# SMS-3923-081-breakout.net
KiCad netlist of a schematic drawn in EAGLE
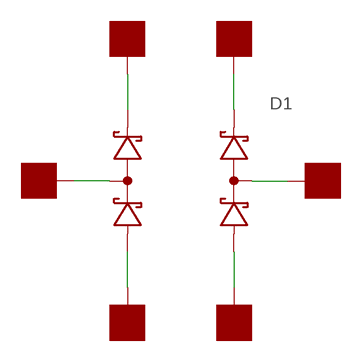
[diagram p0: schematic, sheet 1]

(export (version "E")
  (design (tool "Eeschema 10.0.6"))
  (components
    (comp (ref "D1")
      (value "SMS3923-081")
      (footprint "eagle-import:SC-88")
      (libsource (lib "eagle-import") (part "SMS3923-081"))
    )
    (comp (ref "U$1")
      (value "PAD50MIL")
      (footprint "eagle-import:PAD_50MIL")
      (libsource (lib "eagle-import") (part "PAD50MIL"))
    )
    (comp (ref "U$2")
      (value "PAD50MIL")
      (footprint "eagle-import:PAD_50MIL")
      (libsource (lib "eagle-import") (part "PAD50MIL"))
    )
    (comp (ref "U$3")
      (value "PAD50MIL")
      (footprint "eagle-import:PAD_50MIL")
      (libsource (lib "eagle-import") (part "PAD50MIL"))
    )
    (comp (ref "U$4")
      (value "PAD50MIL")
      (footprint "eagle-import:PAD_50MIL")
      (libsource (lib "eagle-import") (part "PAD50MIL"))
    )
    (comp (ref "U$5")
      (value "PAD50MIL")
      (footprint "eagle-import:PAD_50MIL")
      (libsource (lib "eagle-import") (part "PAD50MIL"))
    )
    (comp (ref "U$6")
      (value "PAD50MIL")
      (footprint "eagle-import:PAD_50MIL")
      (libsource (lib "eagle-import") (part "PAD50MIL"))
    )
  )
  (nets
    (net (code "1") (name "Net-(D1-ANODE0)") (class "Default")
      (node (ref "D1") (pin "1") (pinfunction "ANODE0_1") (pintype "bidirectional"))
      (node (ref "U$4") (pin "P$1") (pinfunction "P$1_P$1") (pintype "bidirectional"))
    )
    (net (code "2") (name "Net-(D1-ANODE1)") (class "Default")
      (node (ref "D1") (pin "6") (pinfunction "ANODE1_6") (pintype "bidirectional"))
      (node (ref "U$3") (pin "P$1") (pinfunction "P$1_P$1") (pintype "bidirectional"))
    )
    (net (code "3") (name "Net-(D1-CATHODE0)") (class "Default")
      (node (ref "D1") (pin "3") (pinfunction "CATHODE0_3") (pintype "bidirectional"))
      (node (ref "U$1") (pin "P$1") (pinfunction "P$1_P$1") (pintype "bidirectional"))
    )
    (net (code "4") (name "Net-(D1-CATHODE1)") (class "Default")
      (node (ref "D1") (pin "4") (pinfunction "CATHODE1_4") (pintype "bidirectional"))
      (node (ref "U$2") (pin "P$1") (pinfunction "P$1_P$1") (pintype "bidirectional"))
    )
    (net (code "5") (name "Net-(D1-COMMON0)") (class "Default")
      (node (ref "D1") (pin "2") (pinfunction "COMMON0_2") (pintype "bidirectional"))
      (node (ref "U$5") (pin "P$1") (pinfunction "P$1_P$1") (pintype "bidirectional"))
    )
    (net (code "6") (name "Net-(D1-COMMON1)") (class "Default")
      (node (ref "D1") (pin "5") (pinfunction "COMMON1_5") (pintype "bidirectional"))
      (node (ref "U$6") (pin "P$1") (pinfunction "P$1_P$1") (pintype "bidirectional"))
    )
  )
)
